# JLINK_OB_TYPEC.net
KiCad netlist of a schematic drawn in Altium Designer
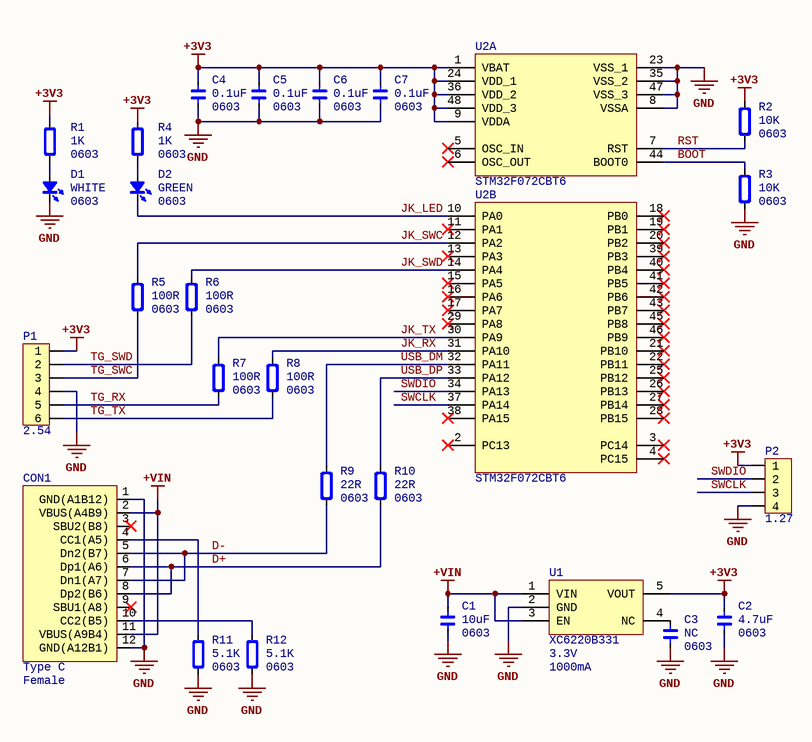
[diagram p0: JLINK_OB_TYPEC.SchDoc]

(export (version "E")
  (design (tool "Eeschema 10.0.6"))
  (components
    (comp (ref "C1")
      (value "10uF")
      (footprint "PCB_PassiveCap:CAP_0603")
      (description "Capacitor")
      (fields (field (name "TYPE") "0603") (field (name "Comment") "C0603"))
      (libsource (lib "SCH_Passive") (part "Cap_0603"))
    )
    (comp (ref "C2")
      (value "4.7uF")
      (footprint "PCB_PassiveCap:CAP_0603")
      (description "Capacitor")
      (fields (field (name "TYPE") "0603") (field (name "Comment") "C0603"))
      (libsource (lib "SCH_Passive") (part "Cap_0603"))
    )
    (comp (ref "C3")
      (value "NC")
      (footprint "PCB_PassiveCap:CAP_0603")
      (description "Capacitor")
      (fields (field (name "TYPE") "0603") (field (name "Comment") "C0603"))
      (libsource (lib "SCH_Passive") (part "Cap_0603"))
    )
    (comp (ref "C4")
      (value "0.1uF")
      (footprint "PCB_PassiveCap:CAP_0603")
      (description "Capacitor")
      (fields (field (name "TYPE") "0603") (field (name "Comment") "C0603"))
      (libsource (lib "SCH_Passive") (part "Cap_0603"))
    )
    (comp (ref "C5")
      (value "0.1uF")
      (footprint "PCB_PassiveCap:CAP_0603")
      (description "Capacitor")
      (fields (field (name "TYPE") "0603") (field (name "Comment") "C0603"))
      (libsource (lib "SCH_Passive") (part "Cap_0603"))
    )
    (comp (ref "C6")
      (value "0.1uF")
      (footprint "PCB_PassiveCap:CAP_0603")
      (description "Capacitor")
      (fields (field (name "TYPE") "0603") (field (name "Comment") "C0603"))
      (libsource (lib "SCH_Passive") (part "Cap_0603"))
    )
    (comp (ref "C7")
      (value "0.1uF")
      (footprint "PCB_PassiveCap:CAP_0603")
      (description "Capacitor")
      (fields (field (name "TYPE") "0603") (field (name "Comment") "C0603"))
      (libsource (lib "SCH_Passive") (part "Cap_0603"))
    )
    (comp (ref "CON1")
      (value "Type C")
      (footprint "PCB_USB_Connector:USB_TypeC_16P")
      (description "USB")
      (fields (field (name "TYPE") "Female") (field (name "Comment") "USB Type C"))
      (libsource (lib "SCH_USB_Connector") (part "USB_TypeC_16P_A"))
    )
    (comp (ref "D1")
      (value "WHITE")
      (footprint "PCB_ActiveLED:LED_0603_YELLOW")
      (description "LED")
      (fields (field (name "TYPE") "0603") (field (name "Comment") "D0603"))
      (libsource (lib "SCH_Active") (part "LED_0603"))
    )
    (comp (ref "D2")
      (value "GREEN")
      (footprint "PCB_ActiveLED:LED_0603_GREEN")
      (description "LED")
      (fields (field (name "TYPE") "0603") (field (name "Comment") "D0603"))
      (libsource (lib "SCH_Active") (part "LED_0603"))
    )
    (comp (ref "P1")
      (value "2.54")
      (footprint "PCB_ConnectorHDR:HDR1X6_2.54_180")
      (description "Header")
      (fields (field (name "Comment") "HDR1x6"))
      (libsource (lib "SCH_ConnectorHDR") (part "HDR1x6_2.54T"))
    )
    (comp (ref "P2")
      (value "1.27")
      (footprint "PCB_ConnectorHDR:HDR1X4_1.27_180")
      (description "Header")
      (fields (field (name "Comment") "HDR1x4"))
      (libsource (lib "SCH_ConnectorHDR") (part "HDR1x4_1.27"))
    )
    (comp (ref "R1")
      (value "1K")
      (footprint "PCB_PassiveRes:RES_0603")
      (description "Resistor")
      (fields (field (name "TYPE") "0603") (field (name "Comment") "R0603"))
      (libsource (lib "SCH_Passive") (part "Res_0603"))
    )
    (comp (ref "R2")
      (value "10K")
      (footprint "PCB_PassiveRes:RES_0603")
      (description "Resistor")
      (fields (field (name "TYPE") "0603") (field (name "Comment") "R0603"))
      (libsource (lib "SCH_Passive") (part "Res_0603"))
    )
    (comp (ref "R3")
      (value "10K")
      (footprint "PCB_PassiveRes:RES_0603")
      (description "Resistor")
      (fields (field (name "TYPE") "0603") (field (name "Comment") "R0603"))
      (libsource (lib "SCH_Passive") (part "Res_0603"))
    )
    (comp (ref "R4")
      (value "1K")
      (footprint "PCB_PassiveRes:RES_0603")
      (description "Resistor")
      (fields (field (name "TYPE") "0603") (field (name "Comment") "R0603"))
      (libsource (lib "SCH_Passive") (part "Res_0603"))
    )
    (comp (ref "R5")
      (value "100R")
      (footprint "PCB_PassiveRes:RES_0603")
      (description "Resistor")
      (fields (field (name "TYPE") "0603") (field (name "Comment") "R0603"))
      (libsource (lib "SCH_Passive") (part "Res_0603"))
    )
    (comp (ref "R6")
      (value "100R")
      (footprint "PCB_PassiveRes:RES_0603")
      (description "Resistor")
      (fields (field (name "TYPE") "0603") (field (name "Comment") "R0603"))
      (libsource (lib "SCH_Passive") (part "Res_0603"))
    )
    (comp (ref "R7")
      (value "100R")
      (footprint "PCB_PassiveRes:RES_0603")
      (description "Resistor")
      (fields (field (name "TYPE") "0603") (field (name "Comment") "R0603"))
      (libsource (lib "SCH_Passive") (part "Res_0603"))
    )
    (comp (ref "R8")
      (value "100R")
      (footprint "PCB_PassiveRes:RES_0603")
      (description "Resistor")
      (fields (field (name "TYPE") "0603") (field (name "Comment") "R0603"))
      (libsource (lib "SCH_Passive") (part "Res_0603"))
    )
    (comp (ref "R9")
      (value "22R")
      (footprint "PCB_PassiveRes:RES_0603")
      (description "Resistor")
      (fields (field (name "TYPE") "0603") (field (name "Comment") "R0603"))
      (libsource (lib "SCH_Passive") (part "Res_0603"))
    )
    (comp (ref "R10")
      (value "22R")
      (footprint "PCB_PassiveRes:RES_0603")
      (description "Resistor")
      (fields (field (name "TYPE") "0603") (field (name "Comment") "R0603"))
      (libsource (lib "SCH_Passive") (part "Res_0603"))
    )
    (comp (ref "R11")
      (value "5.1K")
      (footprint "PCB_PassiveRes:RES_0603")
      (description "Resistor")
      (fields (field (name "TYPE") "0603") (field (name "Comment") "R0603"))
      (libsource (lib "SCH_Passive") (part "Res_0603"))
    )
    (comp (ref "R12")
      (value "5.1K")
      (footprint "PCB_PassiveRes:RES_0603")
      (description "Resistor")
      (fields (field (name "TYPE") "0603") (field (name "Comment") "R0603"))
      (libsource (lib "SCH_Passive") (part "Res_0603"))
    )
    (comp (ref "U1")
      (value "XC6220B331")
      (footprint "PCB_IntegratedCircuit:SOT23-5")
      (description "LDO")
      (fields
        (field (name "ALTIUM_VALUE") "3.3V")
        (field (name "MANUFACTURER") "Torex Semiconductor")
        (field (name "SPECIFICATION") "1000mA")
      )
      (libsource (lib "SCH_Power") (part "XC6220x_SOT25"))
    )
    (comp (ref "U2")
      (value "STM32F072CBT6")
      (footprint "PCB_IntegratedCircuit:LQFP48_P0.5_7.0x7.0")
      (description "MCU ST")
      (fields (field (name "MANUFACTURER") "STMicroelectronics"))
      (libsource (lib "SCH_Microcontroller") (part "STM32F072CxT"))
    )
  )
  (nets
    (net (code "1") (name "+3V3") (class "Default")
      (node (ref "C2") (pin "2") (pinfunction "2_2") (pintype "passive"))
      (node (ref "C4") (pin "2") (pinfunction "2_2") (pintype "passive"))
      (node (ref "C5") (pin "2") (pinfunction "2_2") (pintype "passive"))
      (node (ref "C6") (pin "2") (pinfunction "2_2") (pintype "passive"))
      (node (ref "C7") (pin "2") (pinfunction "2_2") (pintype "passive"))
      (node (ref "P1") (pin "1") (pinfunction "1_1") (pintype "passive"))
      (node (ref "P2") (pin "1") (pinfunction "1_1") (pintype "passive"))
      (node (ref "R1") (pin "2") (pinfunction "2_2") (pintype "passive"))
      (node (ref "R2") (pin "2") (pinfunction "2_2") (pintype "passive"))
      (node (ref "R4") (pin "2") (pinfunction "2_2") (pintype "passive"))
      (node (ref "U1") (pin "5") (pinfunction "VOUT_5") (pintype "passive"))
      (node (ref "U2") (pin "1") (pinfunction "VBAT_1") (pintype "passive"))
      (node (ref "U2") (pin "24") (pinfunction "VDD_1_24") (pintype "passive"))
      (node (ref "U2") (pin "36") (pinfunction "VDD_2_36") (pintype "passive"))
      (node (ref "U2") (pin "48") (pinfunction "VDD_3_48") (pintype "passive"))
      (node (ref "U2") (pin "9") (pinfunction "VDDA_9") (pintype "passive"))
    )
    (net (code "2") (name "+VIN") (class "Default")
      (node (ref "C1") (pin "2") (pinfunction "2_2") (pintype "passive"))
      (node (ref "CON1") (pin "11") (pinfunction "VBUS(A9B4)_11") (pintype "passive"))
      (node (ref "CON1") (pin "2") (pinfunction "VBUS(A4B9)_2") (pintype "passive"))
      (node (ref "U1") (pin "1") (pinfunction "VIN_1") (pintype "passive"))
      (node (ref "U1") (pin "3") (pinfunction "EN_3") (pintype "power_in"))
    )
    (net (code "3") (name "/BOOT") (class "Default")
      (node (ref "R3") (pin "2") (pinfunction "2_2") (pintype "passive"))
      (node (ref "U2") (pin "44") (pinfunction "BOOT0_44") (pintype "passive"))
    )
    (net (code "4") (name "/D+") (class "Default")
      (node (ref "CON1") (pin "6") (pinfunction "Dp1(A6)_6") (pintype "passive"))
      (node (ref "CON1") (pin "8") (pinfunction "Dp2(B6)_8") (pintype "passive"))
      (node (ref "R10") (pin "1") (pinfunction "1_1") (pintype "passive"))
    )
    (net (code "5") (name "/D-") (class "Default")
      (node (ref "CON1") (pin "5") (pinfunction "Dn2(B7)_5") (pintype "passive"))
      (node (ref "CON1") (pin "7") (pinfunction "Dn1(A7)_7") (pintype "passive"))
      (node (ref "R9") (pin "1") (pinfunction "1_1") (pintype "passive"))
    )
    (net (code "6") (name "/JK_LED") (class "Default")
      (node (ref "D2") (pin "2") (pinfunction "CATHODE_2") (pintype "passive"))
      (node (ref "U2") (pin "10") (pinfunction "PA0_10") (pintype "passive"))
    )
    (net (code "7") (name "/JK_RX") (class "Default")
      (node (ref "R8") (pin "2") (pinfunction "2_2") (pintype "passive"))
      (node (ref "U2") (pin "31") (pinfunction "PA10_31") (pintype "passive"))
    )
    (net (code "8") (name "/JK_SWC") (class "Default")
      (node (ref "R5") (pin "2") (pinfunction "2_2") (pintype "passive"))
      (node (ref "U2") (pin "12") (pinfunction "PA2_12") (pintype "passive"))
    )
    (net (code "9") (name "/JK_SWD") (class "Default")
      (node (ref "R6") (pin "2") (pinfunction "2_2") (pintype "passive"))
      (node (ref "U2") (pin "14") (pinfunction "PA4_14") (pintype "passive"))
    )
    (net (code "10") (name "/JK_TX") (class "Default")
      (node (ref "R7") (pin "2") (pinfunction "2_2") (pintype "passive"))
      (node (ref "U2") (pin "30") (pinfunction "PA9_30") (pintype "passive"))
    )
    (net (code "11") (name "/RST") (class "Default")
      (node (ref "R2") (pin "1") (pinfunction "1_1") (pintype "passive"))
      (node (ref "U2") (pin "7") (pinfunction "RST_7") (pintype "passive"))
    )
    (net (code "12") (name "/SWCLK") (class "Default")
      (node (ref "P2") (pin "3") (pinfunction "3_3") (pintype "passive"))
      (node (ref "U2") (pin "37") (pinfunction "PA14_37") (pintype "passive"))
    )
    (net (code "13") (name "/SWDIO") (class "Default")
      (node (ref "P2") (pin "2") (pinfunction "2_2") (pintype "passive"))
      (node (ref "U2") (pin "34") (pinfunction "PA13_34") (pintype "passive"))
    )
    (net (code "14") (name "/TG_RX") (class "Default")
      (node (ref "P1") (pin "5") (pinfunction "5_5") (pintype "passive"))
      (node (ref "R7") (pin "1") (pinfunction "1_1") (pintype "passive"))
    )
    (net (code "15") (name "/TG_SWC") (class "Default")
      (node (ref "P1") (pin "3") (pinfunction "3_3") (pintype "passive"))
      (node (ref "R5") (pin "1") (pinfunction "1_1") (pintype "passive"))
    )
    (net (code "16") (name "/TG_SWD") (class "Default")
      (node (ref "P1") (pin "2") (pinfunction "2_2") (pintype "passive"))
      (node (ref "R6") (pin "1") (pinfunction "1_1") (pintype "passive"))
    )
    (net (code "17") (name "/TG_TX") (class "Default")
      (node (ref "P1") (pin "6") (pinfunction "6_6") (pintype "passive"))
      (node (ref "R8") (pin "1") (pinfunction "1_1") (pintype "passive"))
    )
    (net (code "18") (name "/USB_DM") (class "Default")
      (node (ref "R9") (pin "2") (pinfunction "2_2") (pintype "passive"))
      (node (ref "U2") (pin "32") (pinfunction "PA11_32") (pintype "passive"))
    )
    (net (code "19") (name "/USB_DP") (class "Default")
      (node (ref "R10") (pin "2") (pinfunction "2_2") (pintype "passive"))
      (node (ref "U2") (pin "33") (pinfunction "PA12_33") (pintype "passive"))
    )
    (net (code "20") (name "GND") (class "Default")
      (node (ref "C1") (pin "1") (pinfunction "1_1") (pintype "passive"))
      (node (ref "C2") (pin "1") (pinfunction "1_1") (pintype "passive"))
      (node (ref "C3") (pin "1") (pinfunction "1_1") (pintype "passive"))
      (node (ref "C4") (pin "1") (pinfunction "1_1") (pintype "passive"))
      (node (ref "C5") (pin "1") (pinfunction "1_1") (pintype "passive"))
      (node (ref "C6") (pin "1") (pinfunction "1_1") (pintype "passive"))
      (node (ref "C7") (pin "1") (pinfunction "1_1") (pintype "passive"))
      (node (ref "CON1") (pin "1") (pinfunction "GND(A1B12)_1") (pintype "passive"))
      (node (ref "CON1") (pin "12") (pinfunction "GND(A12B1)_12") (pintype "passive"))
      (node (ref "D1") (pin "2") (pinfunction "CATHODE_2") (pintype "passive"))
      (node (ref "P1") (pin "4") (pinfunction "4_4") (pintype "passive"))
      (node (ref "P2") (pin "4") (pinfunction "4_4") (pintype "passive"))
      (node (ref "R11") (pin "1") (pinfunction "1_1") (pintype "passive"))
      (node (ref "R12") (pin "1") (pinfunction "1_1") (pintype "passive"))
      (node (ref "R3") (pin "1") (pinfunction "1_1") (pintype "passive"))
      (node (ref "U1") (pin "2") (pinfunction "GND_2") (pintype "passive"))
      (node (ref "U2") (pin "23") (pinfunction "VSS_1_23") (pintype "passive"))
      (node (ref "U2") (pin "35") (pinfunction "VSS_2_35") (pintype "passive"))
      (node (ref "U2") (pin "47") (pinfunction "VSS_3_47") (pintype "passive"))
      (node (ref "U2") (pin "8") (pinfunction "VSSA_8") (pintype "passive"))
    )
    (net (code "21") (name "Net-(CON1-CC1(A5))") (class "Default")
      (node (ref "CON1") (pin "4") (pinfunction "CC1(A5)_4") (pintype "passive"))
      (node (ref "R11") (pin "2") (pinfunction "2_2") (pintype "passive"))
    )
    (net (code "22") (name "Net-(CON1-CC2(B5))") (class "Default")
      (node (ref "CON1") (pin "10") (pinfunction "CC2(B5)_10") (pintype "passive"))
      (node (ref "R12") (pin "2") (pinfunction "2_2") (pintype "passive"))
    )
    (net (code "23") (name "Net-(D1-ANODE)") (class "Default")
      (node (ref "D1") (pin "1") (pinfunction "ANODE_1") (pintype "passive"))
      (node (ref "R1") (pin "1") (pinfunction "1_1") (pintype "passive"))
    )
    (net (code "24") (name "Net-(D2-ANODE)") (class "Default")
      (node (ref "D2") (pin "1") (pinfunction "ANODE_1") (pintype "passive"))
      (node (ref "R4") (pin "1") (pinfunction "1_1") (pintype "passive"))
    )
    (net (code "25") (name "Net-(U1-NC)") (class "Default")
      (node (ref "C3") (pin "2") (pinfunction "2_2") (pintype "passive"))
      (node (ref "U1") (pin "4") (pinfunction "NC_4") (pintype "passive"))
    )
    (net (code "26") (name "unconnected-(CON1-PadSH)") (class "Default")
      (node (ref "CON1") (pin "SH") (pinfunction "SH_SH") (pintype "passive"))
    )
    (net (code "27") (name "unconnected-(CON1-SBU1(A8)-Pad9)") (class "Default")
      (node (ref "CON1") (pin "9") (pinfunction "SBU1(A8)_9") (pintype "passive+no_connect"))
    )
    (net (code "28") (name "unconnected-(CON1-SBU2(B8)-Pad3)") (class "Default")
      (node (ref "CON1") (pin "3") (pinfunction "SBU2(B8)_3") (pintype "passive+no_connect"))
    )
    (net (code "29") (name "unconnected-(U2A-OSC_IN-Pad5)") (class "Default")
      (node (ref "U2") (pin "5") (pinfunction "OSC_IN_5") (pintype "passive+no_connect"))
    )
    (net (code "30") (name "unconnected-(U2A-OSC_OUT-Pad6)") (class "Default")
      (node (ref "U2") (pin "6") (pinfunction "OSC_OUT_6") (pintype "passive+no_connect"))
    )
    (net (code "31") (name "unconnected-(U2B-PA1-Pad11)") (class "Default")
      (node (ref "U2") (pin "11") (pinfunction "PA1_11") (pintype "passive+no_connect"))
    )
    (net (code "32") (name "unconnected-(U2B-PA3-Pad13)") (class "Default")
      (node (ref "U2") (pin "13") (pinfunction "PA3_13") (pintype "passive+no_connect"))
    )
    (net (code "33") (name "unconnected-(U2B-PA5-Pad15)") (class "Default")
      (node (ref "U2") (pin "15") (pinfunction "PA5_15") (pintype "passive+no_connect"))
    )
    (net (code "34") (name "unconnected-(U2B-PA6-Pad16)") (class "Default")
      (node (ref "U2") (pin "16") (pinfunction "PA6_16") (pintype "passive+no_connect"))
    )
    (net (code "35") (name "unconnected-(U2B-PA7-Pad17)") (class "Default")
      (node (ref "U2") (pin "17") (pinfunction "PA7_17") (pintype "passive+no_connect"))
    )
    (net (code "36") (name "unconnected-(U2B-PA8-Pad29)") (class "Default")
      (node (ref "U2") (pin "29") (pinfunction "PA8_29") (pintype "passive+no_connect"))
    )
    (net (code "37") (name "unconnected-(U2B-PA15-Pad38)") (class "Default")
      (node (ref "U2") (pin "38") (pinfunction "PA15_38") (pintype "passive+no_connect"))
    )
    (net (code "38") (name "unconnected-(U2B-PB0-Pad18)") (class "Default")
      (node (ref "U2") (pin "18") (pinfunction "PB0_18") (pintype "passive+no_connect"))
    )
    (net (code "39") (name "unconnected-(U2B-PB1-Pad19)") (class "Default")
      (node (ref "U2") (pin "19") (pinfunction "PB1_19") (pintype "passive+no_connect"))
    )
    (net (code "40") (name "unconnected-(U2B-PB2-Pad20)") (class "Default")
      (node (ref "U2") (pin "20") (pinfunction "PB2_20") (pintype "passive+no_connect"))
    )
    (net (code "41") (name "unconnected-(U2B-PB3-Pad39)") (class "Default")
      (node (ref "U2") (pin "39") (pinfunction "PB3_39") (pintype "passive+no_connect"))
    )
    (net (code "42") (name "unconnected-(U2B-PB4-Pad40)") (class "Default")
      (node (ref "U2") (pin "40") (pinfunction "PB4_40") (pintype "passive+no_connect"))
    )
    (net (code "43") (name "unconnected-(U2B-PB5-Pad41)") (class "Default")
      (node (ref "U2") (pin "41") (pinfunction "PB5_41") (pintype "passive+no_connect"))
    )
    (net (code "44") (name "unconnected-(U2B-PB6-Pad42)") (class "Default")
      (node (ref "U2") (pin "42") (pinfunction "PB6_42") (pintype "passive+no_connect"))
    )
    (net (code "45") (name "unconnected-(U2B-PB7-Pad43)") (class "Default")
      (node (ref "U2") (pin "43") (pinfunction "PB7_43") (pintype "passive+no_connect"))
    )
    (net (code "46") (name "unconnected-(U2B-PB8-Pad45)") (class "Default")
      (node (ref "U2") (pin "45") (pinfunction "PB8_45") (pintype "passive+no_connect"))
    )
    (net (code "47") (name "unconnected-(U2B-PB9-Pad46)") (class "Default")
      (node (ref "U2") (pin "46") (pinfunction "PB9_46") (pintype "passive+no_connect"))
    )
    (net (code "48") (name "unconnected-(U2B-PB10-Pad21)") (class "Default")
      (node (ref "U2") (pin "21") (pinfunction "PB10_21") (pintype "passive+no_connect"))
    )
    (net (code "49") (name "unconnected-(U2B-PB11-Pad22)") (class "Default")
      (node (ref "U2") (pin "22") (pinfunction "PB11_22") (pintype "passive+no_connect"))
    )
    (net (code "50") (name "unconnected-(U2B-PB12-Pad25)") (class "Default")
      (node (ref "U2") (pin "25") (pinfunction "PB12_25") (pintype "passive+no_connect"))
    )
    (net (code "51") (name "unconnected-(U2B-PB13-Pad26)") (class "Default")
      (node (ref "U2") (pin "26") (pinfunction "PB13_26") (pintype "passive+no_connect"))
    )
    (net (code "52") (name "unconnected-(U2B-PB14-Pad27)") (class "Default")
      (node (ref "U2") (pin "27") (pinfunction "PB14_27") (pintype "passive+no_connect"))
    )
    (net (code "53") (name "unconnected-(U2B-PB15-Pad28)") (class "Default")
      (node (ref "U2") (pin "28") (pinfunction "PB15_28") (pintype "passive+no_connect"))
    )
    (net (code "54") (name "unconnected-(U2B-PC13-Pad2)") (class "Default")
      (node (ref "U2") (pin "2") (pinfunction "PC13_2") (pintype "passive+no_connect"))
    )
    (net (code "55") (name "unconnected-(U2B-PC14-Pad3)") (class "Default")
      (node (ref "U2") (pin "3") (pinfunction "PC14_3") (pintype "passive+no_connect"))
    )
    (net (code "56") (name "unconnected-(U2B-PC15-Pad4)") (class "Default")
      (node (ref "U2") (pin "4") (pinfunction "PC15_4") (pintype "passive+no_connect"))
    )
  )
)
